# Motor_PCB.net
KiCad netlist of a schematic drawn in EAGLE
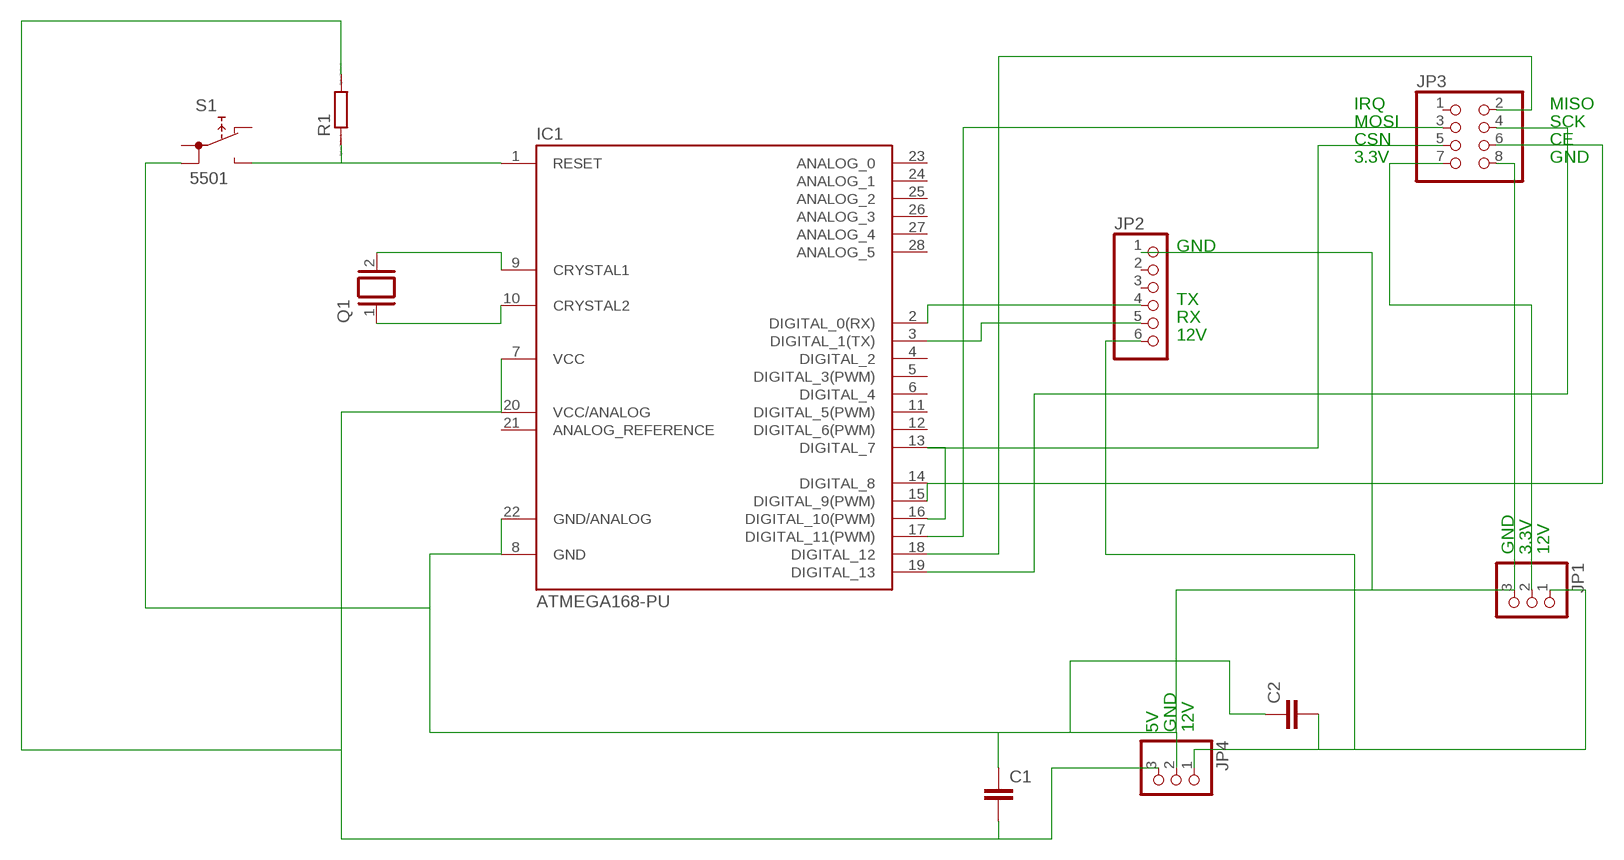
[diagram p0: schematic, sheet 1]

(export (version "E")
  (design (tool "Eeschema 10.0.6"))
  (components
    (comp (ref "C1")
      (value "C2,5-3")
      (footprint "eagle-import:C2.5-3")
      (libsource (lib "eagle-import") (part "C2,5-3"))
    )
    (comp (ref "C2")
      (value "C2,5-3")
      (footprint "eagle-import:C2.5-3")
      (libsource (lib "eagle-import") (part "C2,5-3"))
    )
    (comp (ref "IC1")
      (value "ATMEGA168-PU")
      (footprint "eagle-import:DIL28-3")
      (libsource (lib "eagle-import") (part "ATMEGA168-PU"))
    )
    (comp (ref "JP1")
      (value "PINHD-1X3")
      (footprint "eagle-import:1X03")
      (libsource (lib "eagle-import") (part "PINHD-1X3"))
    )
    (comp (ref "JP2")
      (value "PINHD-1X6")
      (footprint "eagle-import:1X06")
      (libsource (lib "eagle-import") (part "PINHD-1X6"))
    )
    (comp (ref "JP3")
      (value "PINHD-2X4")
      (footprint "eagle-import:2X04")
      (libsource (lib "eagle-import") (part "PINHD-2X4"))
    )
    (comp (ref "JP4")
      (value "PINHD-1X3")
      (footprint "eagle-import:1X03")
      (libsource (lib "eagle-import") (part "PINHD-1X3"))
    )
    (comp (ref "Q1")
      (value "XTAL/S")
      (footprint "eagle-import:QS")
      (libsource (lib "eagle-import") (part "XTAL/S"))
    )
    (comp (ref "R1")
      (value "R0207/10")
      (footprint "eagle-import:0207_10")
      (libsource (lib "eagle-import") (part "R0207/10"))
    )
    (comp (ref "S1")
      (value "5501")
      (footprint "eagle-import:5501")
      (libsource (lib "eagle-import") (part "55?01"))
    )
  )
  (nets
    (net (code "1") (name "Net-(C2-Pad2)") (class "Default")
      (node (ref "C2") (pin "2") (pinfunction "2_2") (pintype "passive"))
      (node (ref "JP1") (pin "1") (pinfunction "1_1") (pintype "passive"))
      (node (ref "JP2") (pin "6") (pinfunction "6_6") (pintype "passive"))
      (node (ref "JP4") (pin "1") (pinfunction "1_1") (pintype "passive"))
    )
    (net (code "2") (name "Net-(IC1-CRYSTAL1)") (class "Default")
      (node (ref "IC1") (pin "9") (pinfunction "CRYSTAL1_9") (pintype "bidirectional"))
      (node (ref "Q1") (pin "2") (pinfunction "2_2") (pintype "passive"))
    )
    (net (code "3") (name "Net-(IC1-CRYSTAL2)") (class "Default")
      (node (ref "IC1") (pin "10") (pinfunction "CRYSTAL2_10") (pintype "bidirectional"))
      (node (ref "Q1") (pin "1") (pinfunction "1_1") (pintype "passive"))
    )
    (net (code "4") (name "Net-(IC1-DIGITAL_0(RX))") (class "Default")
      (node (ref "IC1") (pin "2") (pinfunction "DIGITAL_0(RX)_2") (pintype "bidirectional"))
      (node (ref "JP2") (pin "4") (pinfunction "4_4") (pintype "passive"))
    )
    (net (code "5") (name "Net-(IC1-DIGITAL_1(TX))") (class "Default")
      (node (ref "IC1") (pin "3") (pinfunction "DIGITAL_1(TX)_3") (pintype "bidirectional"))
      (node (ref "JP2") (pin "5") (pinfunction "5_5") (pintype "passive"))
    )
    (net (code "6") (name "Net-(IC1-DIGITAL_8)") (class "Default")
      (node (ref "IC1") (pin "14") (pinfunction "DIGITAL_8_14") (pintype "bidirectional"))
      (node (ref "IC1") (pin "15") (pinfunction "DIGITAL_9(PWM)_15") (pintype "bidirectional"))
      (node (ref "JP3") (pin "6") (pinfunction "6_6") (pintype "passive"))
    )
    (net (code "7") (name "Net-(IC1-DIGITAL_10(PWM))") (class "Default")
      (node (ref "IC1") (pin "13") (pinfunction "DIGITAL_7_13") (pintype "bidirectional"))
      (node (ref "IC1") (pin "16") (pinfunction "DIGITAL_10(PWM)_16") (pintype "bidirectional"))
      (node (ref "JP3") (pin "5") (pinfunction "5_5") (pintype "passive"))
    )
    (net (code "8") (name "Net-(IC1-DIGITAL_11(PWM))") (class "Default")
      (node (ref "IC1") (pin "17") (pinfunction "DIGITAL_11(PWM)_17") (pintype "bidirectional"))
      (node (ref "JP3") (pin "3") (pinfunction "3_3") (pintype "passive"))
    )
    (net (code "9") (name "Net-(IC1-DIGITAL_12)") (class "Default")
      (node (ref "IC1") (pin "18") (pinfunction "DIGITAL_12_18") (pintype "bidirectional"))
      (node (ref "JP3") (pin "2") (pinfunction "2_2") (pintype "passive"))
    )
    (net (code "10") (name "Net-(IC1-DIGITAL_13)") (class "Default")
      (node (ref "IC1") (pin "19") (pinfunction "DIGITAL_13_19") (pintype "bidirectional"))
      (node (ref "JP3") (pin "4") (pinfunction "4_4") (pintype "passive"))
    )
    (net (code "11") (name "Net-(IC1-GND)") (class "Default")
      (node (ref "C1") (pin "1") (pinfunction "1_1") (pintype "passive"))
      (node (ref "C2") (pin "1") (pinfunction "1_1") (pintype "passive"))
      (node (ref "IC1") (pin "22") (pinfunction "GND/ANALOG_22") (pintype "power_in"))
      (node (ref "IC1") (pin "8") (pinfunction "GND_8") (pintype "power_in"))
      (node (ref "JP1") (pin "3") (pinfunction "3_3") (pintype "passive"))
      (node (ref "JP2") (pin "1") (pinfunction "1_1") (pintype "passive"))
      (node (ref "JP3") (pin "8") (pinfunction "8_8") (pintype "passive"))
      (node (ref "JP4") (pin "2") (pinfunction "2_2") (pintype "passive"))
      (node (ref "S1") (pin "1B") (pinfunction "1B_1B") (pintype "passive"))
    )
    (net (code "12") (name "Net-(IC1-RESET)") (class "Default")
      (node (ref "IC1") (pin "1") (pinfunction "RESET_1") (pintype "bidirectional"))
      (node (ref "R1") (pin "1") (pinfunction "1_1") (pintype "passive"))
      (node (ref "S1") (pin "NO") (pinfunction "NO_NO") (pintype "passive"))
    )
    (net (code "13") (name "Net-(IC1-VCC)") (class "Default")
      (node (ref "C1") (pin "2") (pinfunction "2_2") (pintype "passive"))
      (node (ref "IC1") (pin "20") (pinfunction "VCC/ANALOG_20") (pintype "passive"))
      (node (ref "IC1") (pin "7") (pinfunction "VCC_7") (pintype "power_in"))
      (node (ref "JP4") (pin "3") (pinfunction "3_3") (pintype "passive"))
      (node (ref "R1") (pin "2") (pinfunction "2_2") (pintype "passive"))
    )
    (net (code "14") (name "Net-(JP1-Pad2)") (class "Default")
      (node (ref "JP1") (pin "2") (pinfunction "2_2") (pintype "passive"))
      (node (ref "JP3") (pin "7") (pinfunction "7_7") (pintype "passive"))
    )
    (net (code "15") (name "unconnected-(IC1-ANALOG_0-Pad23)") (class "Default")
      (node (ref "IC1") (pin "23") (pinfunction "ANALOG_0_23") (pintype "bidirectional"))
    )
    (net (code "16") (name "unconnected-(IC1-ANALOG_1-Pad24)") (class "Default")
      (node (ref "IC1") (pin "24") (pinfunction "ANALOG_1_24") (pintype "bidirectional"))
    )
    (net (code "17") (name "unconnected-(IC1-ANALOG_2-Pad25)") (class "Default")
      (node (ref "IC1") (pin "25") (pinfunction "ANALOG_2_25") (pintype "bidirectional"))
    )
    (net (code "18") (name "unconnected-(IC1-ANALOG_3-Pad26)") (class "Default")
      (node (ref "IC1") (pin "26") (pinfunction "ANALOG_3_26") (pintype "bidirectional"))
    )
    (net (code "19") (name "unconnected-(IC1-ANALOG_4-Pad27)") (class "Default")
      (node (ref "IC1") (pin "27") (pinfunction "ANALOG_4_27") (pintype "bidirectional"))
    )
    (net (code "20") (name "unconnected-(IC1-ANALOG_5-Pad28)") (class "Default")
      (node (ref "IC1") (pin "28") (pinfunction "ANALOG_5_28") (pintype "bidirectional"))
    )
    (net (code "21") (name "unconnected-(IC1-ANALOG_REFERENCE-Pad21)") (class "Default")
      (node (ref "IC1") (pin "21") (pinfunction "ANALOG_REFERENCE_21") (pintype "passive"))
    )
    (net (code "22") (name "unconnected-(IC1-DIGITAL_2-Pad4)") (class "Default")
      (node (ref "IC1") (pin "4") (pinfunction "DIGITAL_2_4") (pintype "bidirectional"))
    )
    (net (code "23") (name "unconnected-(IC1-DIGITAL_3(PWM)-Pad5)") (class "Default")
      (node (ref "IC1") (pin "5") (pinfunction "DIGITAL_3(PWM)_5") (pintype "bidirectional"))
    )
    (net (code "24") (name "unconnected-(IC1-DIGITAL_4-Pad6)") (class "Default")
      (node (ref "IC1") (pin "6") (pinfunction "DIGITAL_4_6") (pintype "bidirectional"))
    )
    (net (code "25") (name "unconnected-(IC1-DIGITAL_5(PWM)-Pad11)") (class "Default")
      (node (ref "IC1") (pin "11") (pinfunction "DIGITAL_5(PWM)_11") (pintype "bidirectional"))
    )
    (net (code "26") (name "unconnected-(IC1-DIGITAL_6(PWM)-Pad12)") (class "Default")
      (node (ref "IC1") (pin "12") (pinfunction "DIGITAL_6(PWM)_12") (pintype "bidirectional"))
    )
    (net (code "27") (name "unconnected-(JP2-Pad2)") (class "Default")
      (node (ref "JP2") (pin "2") (pinfunction "2_2") (pintype "passive"))
    )
    (net (code "28") (name "unconnected-(JP2-Pad3)") (class "Default")
      (node (ref "JP2") (pin "3") (pinfunction "3_3") (pintype "passive"))
    )
    (net (code "29") (name "unconnected-(JP3-Pad1)") (class "Default")
      (node (ref "JP3") (pin "1") (pinfunction "1_1") (pintype "passive"))
    )
    (net (code "30") (name "unconnected-(S1-Pad1A)") (class "Default")
      (node (ref "S1") (pin "1A") (pinfunction "1A_1A") (pintype "passive"))
    )
    (net (code "31") (name "unconnected-(S1-PadNC)") (class "Default")
      (node (ref "S1") (pin "NC") (pinfunction "NC_NC") (pintype "passive"))
    )
  )
)
